# real_watch_1v1_displayboard.net
KiCad netlist of a schematic drawn in Altium Designer
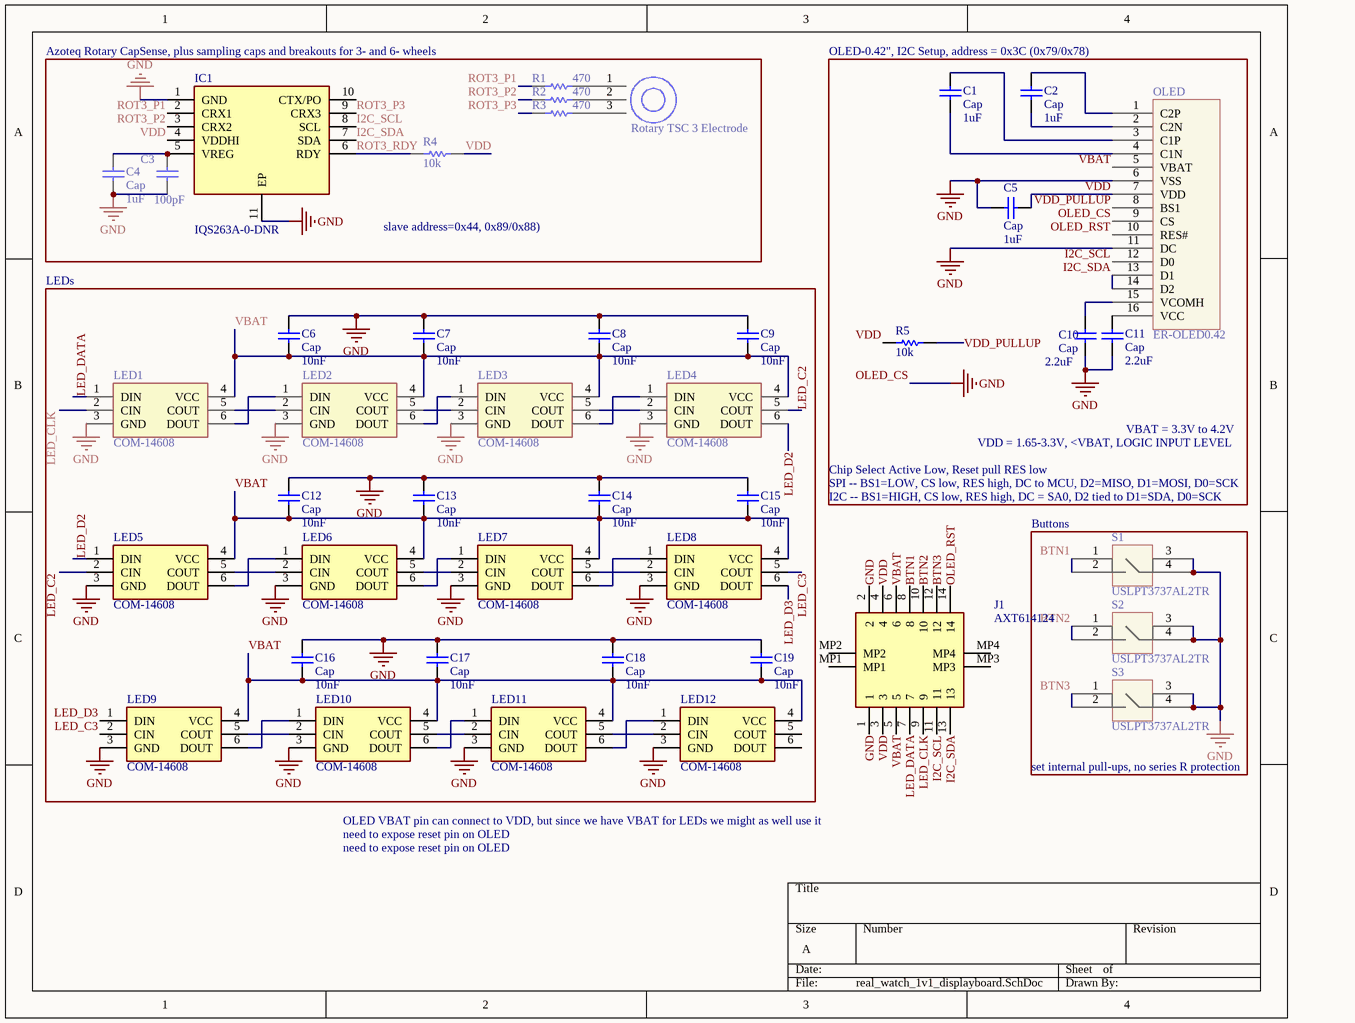
[diagram p0: real_watch_1v1_displayboard.SchDoc]

(export (version "E")
  (design (tool "Eeschema 10.0.6"))
  (components
    (comp (ref "C1")
      (value "Cap")
      (footprint "0402C")
      (description "Capacitor")
      (fields (field (name "ALTIUM_VALUE") "1uF") (field (name "PUBLISHER") "Altium Limited"))
      (libsource (lib "Miscellaneous Devices") (part "Cap"))
    )
    (comp (ref "C2")
      (value "Cap")
      (footprint "0402C")
      (description "Capacitor")
      (fields (field (name "ALTIUM_VALUE") "1uF") (field (name "PUBLISHER") "Altium Limited"))
      (libsource (lib "Miscellaneous Devices") (part "Cap"))
    )
    (comp (ref "C3")
      (value "100pF")
      (footprint "0402C")
      (description "Capacitor")
      (fields (field (name "Comment") "Cap") (field (name "PUBLISHER") "Altium Limited"))
      (libsource (lib "Miscellaneous Devices") (part "Cap"))
    )
    (comp (ref "C4")
      (value "Cap")
      (footprint "0402C")
      (description "Capacitor")
      (fields (field (name "ALTIUM_VALUE") "1uF") (field (name "PUBLISHER") "Altium Limited"))
      (libsource (lib "Miscellaneous Devices") (part "Cap"))
    )
    (comp (ref "C5")
      (value "Cap")
      (footprint "0402C")
      (description "Capacitor")
      (fields (field (name "ALTIUM_VALUE") "1uF") (field (name "PUBLISHER") "Altium Limited"))
      (libsource (lib "Miscellaneous Devices") (part "Cap"))
    )
    (comp (ref "C6")
      (value "Cap")
      (footprint "0402C")
      (description "Capacitor")
      (fields (field (name "ALTIUM_VALUE") "10nF") (field (name "PUBLISHER") "Altium Limited"))
      (libsource (lib "Miscellaneous Devices") (part "Cap"))
    )
    (comp (ref "C7")
      (value "Cap")
      (footprint "0402C")
      (description "Capacitor")
      (fields (field (name "ALTIUM_VALUE") "10nF") (field (name "PUBLISHER") "Altium Limited"))
      (libsource (lib "Miscellaneous Devices") (part "Cap"))
    )
    (comp (ref "C8")
      (value "Cap")
      (footprint "0402C")
      (description "Capacitor")
      (fields (field (name "ALTIUM_VALUE") "10nF") (field (name "PUBLISHER") "Altium Limited"))
      (libsource (lib "Miscellaneous Devices") (part "Cap"))
    )
    (comp (ref "C9")
      (value "Cap")
      (footprint "0402C")
      (description "Capacitor")
      (fields (field (name "ALTIUM_VALUE") "10nF") (field (name "PUBLISHER") "Altium Limited"))
      (libsource (lib "Miscellaneous Devices") (part "Cap"))
    )
    (comp (ref "C10")
      (value "Cap")
      (footprint "0402C")
      (description "Capacitor")
      (fields (field (name "ALTIUM_VALUE") "2.2uF") (field (name "PUBLISHER") "Altium Limited"))
      (libsource (lib "Miscellaneous Devices") (part "Cap"))
    )
    (comp (ref "C11")
      (value "Cap")
      (footprint "0402C")
      (description "Capacitor")
      (fields (field (name "ALTIUM_VALUE") "2.2uF") (field (name "PUBLISHER") "Altium Limited"))
      (libsource (lib "Miscellaneous Devices") (part "Cap"))
    )
    (comp (ref "C12")
      (value "Cap")
      (footprint "0402C")
      (description "Capacitor")
      (fields (field (name "ALTIUM_VALUE") "10nF") (field (name "PUBLISHER") "Altium Limited"))
      (libsource (lib "Miscellaneous Devices") (part "Cap"))
    )
    (comp (ref "C13")
      (value "Cap")
      (footprint "0402C")
      (description "Capacitor")
      (fields (field (name "ALTIUM_VALUE") "10nF") (field (name "PUBLISHER") "Altium Limited"))
      (libsource (lib "Miscellaneous Devices") (part "Cap"))
    )
    (comp (ref "C14")
      (value "Cap")
      (footprint "0402C")
      (description "Capacitor")
      (fields (field (name "ALTIUM_VALUE") "10nF") (field (name "PUBLISHER") "Altium Limited"))
      (libsource (lib "Miscellaneous Devices") (part "Cap"))
    )
    (comp (ref "C15")
      (value "Cap")
      (footprint "0402C")
      (description "Capacitor")
      (fields (field (name "ALTIUM_VALUE") "10nF") (field (name "PUBLISHER") "Altium Limited"))
      (libsource (lib "Miscellaneous Devices") (part "Cap"))
    )
    (comp (ref "C16")
      (value "Cap")
      (footprint "0402C")
      (description "Capacitor")
      (fields (field (name "ALTIUM_VALUE") "10nF") (field (name "PUBLISHER") "Altium Limited"))
      (libsource (lib "Miscellaneous Devices") (part "Cap"))
    )
    (comp (ref "C17")
      (value "Cap")
      (footprint "0402C")
      (description "Capacitor")
      (fields (field (name "ALTIUM_VALUE") "10nF") (field (name "PUBLISHER") "Altium Limited"))
      (libsource (lib "Miscellaneous Devices") (part "Cap"))
    )
    (comp (ref "C18")
      (value "Cap")
      (footprint "0402C")
      (description "Capacitor")
      (fields (field (name "ALTIUM_VALUE") "10nF") (field (name "PUBLISHER") "Altium Limited"))
      (libsource (lib "Miscellaneous Devices") (part "Cap"))
    )
    (comp (ref "C19")
      (value "Cap")
      (footprint "0402C")
      (description "Capacitor")
      (fields (field (name "ALTIUM_VALUE") "10nF") (field (name "PUBLISHER") "Altium Limited"))
      (libsource (lib "Miscellaneous Devices") (part "Cap"))
    )
    (comp (ref "IC1")
      (value "IQS263A-0-DNR")
      (footprint "SamacSys:SON50P300X300X80-11N-D")
      (description "Integrated Circuit")
      (libsource (lib "SamacSys") (part "IQS263A-0-DNR"))
    )
    (comp (ref "J1")
      (value "AXT614124")
      (footprint "SamacSys:AXT614124")
      (description "Connector")
      (fields (field (name "MOUSER PART NUMBER") "769-AXT614124"))
      (libsource (lib "*") (part "AXT614124"))
    )
    (comp (ref "LED1")
      (value "COM-14608")
      (footprint "SamacSys:SON75P200X200X100-6N")
      (description "LED")
      (fields (field (name "MOUSER PART NUMBER") "474-COM-14608"))
      (libsource (lib "*") (part "COM-14608"))
    )
    (comp (ref "LED2")
      (value "COM-14608")
      (footprint "SamacSys:SON75P200X200X100-6N")
      (description "LED")
      (fields (field (name "MOUSER PART NUMBER") "474-COM-14608"))
      (libsource (lib "*") (part "COM-14608"))
    )
    (comp (ref "LED3")
      (value "COM-14608")
      (footprint "SamacSys:SON75P200X200X100-6N")
      (description "LED")
      (fields (field (name "MOUSER PART NUMBER") "474-COM-14608"))
      (libsource (lib "*") (part "COM-14608"))
    )
    (comp (ref "LED4")
      (value "COM-14608")
      (footprint "SamacSys:SON75P200X200X100-6N")
      (description "LED")
      (fields (field (name "MOUSER PART NUMBER") "474-COM-14608"))
      (libsource (lib "*") (part "COM-14608"))
    )
    (comp (ref "LED5")
      (value "COM-14608")
      (footprint "SamacSys:SON75P200X200X100-6N")
      (description "LED")
      (fields (field (name "MOUSER PART NUMBER") "474-COM-14608"))
      (libsource (lib "*") (part "COM-14608"))
    )
    (comp (ref "LED6")
      (value "COM-14608")
      (footprint "SamacSys:SON75P200X200X100-6N")
      (description "LED")
      (fields (field (name "MOUSER PART NUMBER") "474-COM-14608"))
      (libsource (lib "*") (part "COM-14608"))
    )
    (comp (ref "LED7")
      (value "COM-14608")
      (footprint "SamacSys:SON75P200X200X100-6N")
      (description "LED")
      (fields (field (name "MOUSER PART NUMBER") "474-COM-14608"))
      (libsource (lib "*") (part "COM-14608"))
    )
    (comp (ref "LED8")
      (value "COM-14608")
      (footprint "SamacSys:SON75P200X200X100-6N")
      (description "LED")
      (fields (field (name "MOUSER PART NUMBER") "474-COM-14608"))
      (libsource (lib "*") (part "COM-14608"))
    )
    (comp (ref "LED9")
      (value "COM-14608")
      (footprint "SamacSys:SON75P200X200X100-6N")
      (description "LED")
      (fields (field (name "MOUSER PART NUMBER") "474-COM-14608"))
      (libsource (lib "*") (part "COM-14608"))
    )
    (comp (ref "LED10")
      (value "COM-14608")
      (footprint "SamacSys:SON75P200X200X100-6N")
      (description "LED")
      (fields (field (name "MOUSER PART NUMBER") "474-COM-14608"))
      (libsource (lib "*") (part "COM-14608"))
    )
    (comp (ref "LED11")
      (value "COM-14608")
      (footprint "SamacSys:SON75P200X200X100-6N")
      (description "LED")
      (fields (field (name "MOUSER PART NUMBER") "474-COM-14608"))
      (libsource (lib "*") (part "COM-14608"))
    )
    (comp (ref "LED12")
      (value "COM-14608")
      (footprint "SamacSys:SON75P200X200X100-6N")
      (description "LED")
      (fields (field (name "MOUSER PART NUMBER") "474-COM-14608"))
      (libsource (lib "*") (part "COM-14608"))
    )
    (comp (ref "OLED")
      (value "ER-OLED0.42")
      (footprint "ER-OLED-0.42")
      (description "BuyDisplay.com 0.42\" OLED Screen I2C/SPI")
      (libsource (lib "david_custom") (part "ER-OLED0.42"))
    )
    (comp (ref "R1")
      (value "470")
      (footprint "0402R")
      (libsource (lib "glasses_full_v1_small") (part "Resistor"))
    )
    (comp (ref "R2")
      (value "470")
      (footprint "0402R")
      (libsource (lib "glasses_full_v1_small") (part "Resistor"))
    )
    (comp (ref "R3")
      (value "470")
      (footprint "0402R")
      (libsource (lib "glasses_full_v1_small") (part "Resistor"))
    )
    (comp (ref "R4")
      (value "10k")
      (footprint "0402R")
      (libsource (lib "glasses_full_v1_small") (part "Resistor"))
    )
    (comp (ref "R5")
      (value "10k")
      (footprint "0402R")
      (libsource (lib "glasses_full_v1_small") (part "Resistor"))
    )
    (comp (ref "ROT1")
      (value "Rotary TSC 3 Electrode")
      (footprint "rotary_touch 3 electrode")
      (libsource (lib "david_custom") (part "Rotary TSC 3 Electrode"))
    )
    (comp (ref "S1")
      (value "USLPT3737AL2TR")
      (footprint "USLPT3737")
      (description "TE 0.35mm low profile switch")
      (libsource (lib "david_custom") (part "USLPT3737AL2TR"))
    )
    (comp (ref "S2")
      (value "USLPT3737AL2TR")
      (footprint "USLPT3737")
      (description "TE 0.35mm low profile switch")
      (libsource (lib "david_custom") (part "USLPT3737AL2TR"))
    )
    (comp (ref "S3")
      (value "USLPT3737AL2TR")
      (footprint "USLPT3737")
      (description "TE 0.35mm low profile switch")
      (libsource (lib "david_custom") (part "USLPT3737AL2TR"))
    )
  )
  (nets
    (net (code "1") (name "/BTN1") (class "Default")
      (node (ref "J1") (pin "8") (pinfunction "8_8") (pintype "passive"))
      (node (ref "S1") (pin "1") (pinfunction "L_1") (pintype "passive"))
      (node (ref "S1") (pin "2") (pinfunction "L_2") (pintype "passive"))
    )
    (net (code "2") (name "/BTN2") (class "Default")
      (node (ref "J1") (pin "10") (pinfunction "10_10") (pintype "passive"))
      (node (ref "S2") (pin "1") (pinfunction "L_1") (pintype "passive"))
      (node (ref "S2") (pin "2") (pinfunction "L_2") (pintype "passive"))
    )
    (net (code "3") (name "/BTN3") (class "Default")
      (node (ref "J1") (pin "12") (pinfunction "12_12") (pintype "passive"))
      (node (ref "S3") (pin "1") (pinfunction "L_1") (pintype "passive"))
      (node (ref "S3") (pin "2") (pinfunction "L_2") (pintype "passive"))
    )
    (net (code "4") (name "/I2C_SCL") (class "Default")
      (node (ref "IC1") (pin "8") (pinfunction "SCL_8") (pintype "passive"))
      (node (ref "J1") (pin "11") (pinfunction "11_11") (pintype "passive"))
      (node (ref "OLED") (pin "12") (pinfunction "D0_12") (pintype "passive"))
    )
    (net (code "5") (name "/I2C_SDA") (class "Default")
      (node (ref "IC1") (pin "7") (pinfunction "SDA_7") (pintype "passive"))
      (node (ref "J1") (pin "13") (pinfunction "13_13") (pintype "passive"))
      (node (ref "OLED") (pin "13") (pinfunction "D1_13") (pintype "passive"))
      (node (ref "OLED") (pin "14") (pinfunction "D2_14") (pintype "passive"))
    )
    (net (code "6") (name "/LED_C2") (class "Default")
      (node (ref "LED4") (pin "5") (pinfunction "COUT_5") (pintype "passive"))
      (node (ref "LED5") (pin "2") (pinfunction "CIN_2") (pintype "passive"))
    )
    (net (code "7") (name "/LED_C3") (class "Default")
      (node (ref "LED8") (pin "5") (pinfunction "COUT_5") (pintype "passive"))
      (node (ref "LED9") (pin "2") (pinfunction "CIN_2") (pintype "passive"))
    )
    (net (code "8") (name "/LED_CLK") (class "Default")
      (node (ref "J1") (pin "9") (pinfunction "9_9") (pintype "passive"))
      (node (ref "LED1") (pin "2") (pinfunction "CIN_2") (pintype "passive"))
    )
    (net (code "9") (name "/LED_D2") (class "Default")
      (node (ref "LED4") (pin "6") (pinfunction "DOUT_6") (pintype "passive"))
      (node (ref "LED5") (pin "1") (pinfunction "DIN_1") (pintype "passive"))
    )
    (net (code "10") (name "/LED_D3") (class "Default")
      (node (ref "LED8") (pin "6") (pinfunction "DOUT_6") (pintype "passive"))
      (node (ref "LED9") (pin "1") (pinfunction "DIN_1") (pintype "passive"))
    )
    (net (code "11") (name "/LED_DATA") (class "Default")
      (node (ref "J1") (pin "7") (pinfunction "7_7") (pintype "passive"))
      (node (ref "LED1") (pin "1") (pinfunction "DIN_1") (pintype "passive"))
    )
    (net (code "12") (name "/OLED_RST") (class "Default")
      (node (ref "J1") (pin "14") (pinfunction "14_14") (pintype "passive"))
      (node (ref "OLED") (pin "10") (pinfunction "RES#_10") (pintype "passive"))
    )
    (net (code "13") (name "/ROT3_P1") (class "Default")
      (node (ref "IC1") (pin "2") (pinfunction "CRX1_2") (pintype "passive"))
      (node (ref "R1") (pin "2") (pinfunction "2_2") (pintype "passive"))
    )
    (net (code "14") (name "/ROT3_P2") (class "Default")
      (node (ref "IC1") (pin "3") (pinfunction "CRX2_3") (pintype "passive"))
      (node (ref "R2") (pin "2") (pinfunction "2_2") (pintype "passive"))
    )
    (net (code "15") (name "/ROT3_P3") (class "Default")
      (node (ref "IC1") (pin "9") (pinfunction "CRX3_9") (pintype "passive"))
      (node (ref "R3") (pin "2") (pinfunction "2_2") (pintype "passive"))
    )
    (net (code "16") (name "/ROT3_RDY") (class "Default")
      (node (ref "IC1") (pin "6") (pinfunction "RDY_6") (pintype "passive"))
      (node (ref "R4") (pin "1") (pinfunction "1_1") (pintype "passive"))
    )
    (net (code "17") (name "/VBAT") (class "Default")
      (node (ref "C12") (pin "1") (pinfunction "1_1") (pintype "passive"))
      (node (ref "C13") (pin "1") (pinfunction "1_1") (pintype "passive"))
      (node (ref "C14") (pin "1") (pinfunction "1_1") (pintype "passive"))
      (node (ref "C15") (pin "1") (pinfunction "1_1") (pintype "passive"))
      (node (ref "C16") (pin "1") (pinfunction "1_1") (pintype "passive"))
      (node (ref "C17") (pin "1") (pinfunction "1_1") (pintype "passive"))
      (node (ref "C18") (pin "1") (pinfunction "1_1") (pintype "passive"))
      (node (ref "C19") (pin "1") (pinfunction "1_1") (pintype "passive"))
      (node (ref "C6") (pin "1") (pinfunction "1_1") (pintype "passive"))
      (node (ref "C7") (pin "1") (pinfunction "1_1") (pintype "passive"))
      (node (ref "C8") (pin "1") (pinfunction "1_1") (pintype "passive"))
      (node (ref "C9") (pin "1") (pinfunction "1_1") (pintype "passive"))
      (node (ref "J1") (pin "5") (pinfunction "5_5") (pintype "passive"))
      (node (ref "J1") (pin "6") (pinfunction "6_6") (pintype "passive"))
      (node (ref "LED1") (pin "4") (pinfunction "VCC_4") (pintype "passive"))
      (node (ref "LED10") (pin "4") (pinfunction "VCC_4") (pintype "passive"))
      (node (ref "LED11") (pin "4") (pinfunction "VCC_4") (pintype "passive"))
      (node (ref "LED12") (pin "4") (pinfunction "VCC_4") (pintype "passive"))
      (node (ref "LED2") (pin "4") (pinfunction "VCC_4") (pintype "passive"))
      (node (ref "LED3") (pin "4") (pinfunction "VCC_4") (pintype "passive"))
      (node (ref "LED4") (pin "4") (pinfunction "VCC_4") (pintype "passive"))
      (node (ref "LED5") (pin "4") (pinfunction "VCC_4") (pintype "passive"))
      (node (ref "LED6") (pin "4") (pinfunction "VCC_4") (pintype "passive"))
      (node (ref "LED7") (pin "4") (pinfunction "VCC_4") (pintype "passive"))
      (node (ref "LED8") (pin "4") (pinfunction "VCC_4") (pintype "passive"))
      (node (ref "LED9") (pin "4") (pinfunction "VCC_4") (pintype "passive"))
      (node (ref "OLED") (pin "5") (pinfunction "VBAT_5") (pintype "power_in"))
    )
    (net (code "18") (name "/VDD") (class "Default")
      (node (ref "C5") (pin "2") (pinfunction "2_2") (pintype "passive"))
      (node (ref "IC1") (pin "4") (pinfunction "VDDHI_4") (pintype "passive"))
      (node (ref "J1") (pin "3") (pinfunction "3_3") (pintype "passive"))
      (node (ref "J1") (pin "4") (pinfunction "4_4") (pintype "passive"))
      (node (ref "OLED") (pin "7") (pinfunction "VDD_7") (pintype "passive"))
      (node (ref "R4") (pin "2") (pinfunction "2_2") (pintype "passive"))
      (node (ref "R5") (pin "1") (pinfunction "1_1") (pintype "passive"))
    )
    (net (code "19") (name "/VDD_PULLUP") (class "Default")
      (node (ref "OLED") (pin "8") (pinfunction "BS1_8") (pintype "passive"))
      (node (ref "R5") (pin "2") (pinfunction "2_2") (pintype "passive"))
    )
    (net (code "20") (name "GND") (class "Default")
      (node (ref "C10") (pin "1") (pinfunction "1_1") (pintype "passive"))
      (node (ref "C11") (pin "1") (pinfunction "1_1") (pintype "passive"))
      (node (ref "C12") (pin "2") (pinfunction "2_2") (pintype "passive"))
      (node (ref "C13") (pin "2") (pinfunction "2_2") (pintype "passive"))
      (node (ref "C14") (pin "2") (pinfunction "2_2") (pintype "passive"))
      (node (ref "C15") (pin "2") (pinfunction "2_2") (pintype "passive"))
      (node (ref "C16") (pin "2") (pinfunction "2_2") (pintype "passive"))
      (node (ref "C17") (pin "2") (pinfunction "2_2") (pintype "passive"))
      (node (ref "C18") (pin "2") (pinfunction "2_2") (pintype "passive"))
      (node (ref "C19") (pin "2") (pinfunction "2_2") (pintype "passive"))
      (node (ref "C3") (pin "1") (pinfunction "1_1") (pintype "passive"))
      (node (ref "C4") (pin "1") (pinfunction "1_1") (pintype "passive"))
      (node (ref "C5") (pin "1") (pinfunction "1_1") (pintype "passive"))
      (node (ref "C6") (pin "2") (pinfunction "2_2") (pintype "passive"))
      (node (ref "C7") (pin "2") (pinfunction "2_2") (pintype "passive"))
      (node (ref "C8") (pin "2") (pinfunction "2_2") (pintype "passive"))
      (node (ref "C9") (pin "2") (pinfunction "2_2") (pintype "passive"))
      (node (ref "IC1") (pin "1") (pinfunction "GND_1") (pintype "passive"))
      (node (ref "IC1") (pin "11") (pinfunction "EP_11") (pintype "passive"))
      (node (ref "J1") (pin "1") (pinfunction "1_1") (pintype "passive"))
      (node (ref "J1") (pin "2") (pinfunction "2_2") (pintype "passive"))
      (node (ref "LED1") (pin "3") (pinfunction "GND_3") (pintype "passive"))
      (node (ref "LED10") (pin "3") (pinfunction "GND_3") (pintype "passive"))
      (node (ref "LED11") (pin "3") (pinfunction "GND_3") (pintype "passive"))
      (node (ref "LED12") (pin "3") (pinfunction "GND_3") (pintype "passive"))
      (node (ref "LED2") (pin "3") (pinfunction "GND_3") (pintype "passive"))
      (node (ref "LED3") (pin "3") (pinfunction "GND_3") (pintype "passive"))
      (node (ref "LED4") (pin "3") (pinfunction "GND_3") (pintype "passive"))
      (node (ref "LED5") (pin "3") (pinfunction "GND_3") (pintype "passive"))
      (node (ref "LED6") (pin "3") (pinfunction "GND_3") (pintype "passive"))
      (node (ref "LED7") (pin "3") (pinfunction "GND_3") (pintype "passive"))
      (node (ref "LED8") (pin "3") (pinfunction "GND_3") (pintype "passive"))
      (node (ref "LED9") (pin "3") (pinfunction "GND_3") (pintype "passive"))
      (node (ref "OLED") (pin "11") (pinfunction "DC_11") (pintype "passive"))
      (node (ref "OLED") (pin "6") (pinfunction "VSS_6") (pintype "passive"))
      (node (ref "OLED") (pin "9") (pinfunction "CS_9") (pintype "passive"))
      (node (ref "S1") (pin "3") (pinfunction "R_3") (pintype "passive"))
      (node (ref "S1") (pin "4") (pinfunction "R_4") (pintype "passive"))
      (node (ref "S2") (pin "3") (pinfunction "R_3") (pintype "passive"))
      (node (ref "S2") (pin "4") (pinfunction "R_4") (pintype "passive"))
      (node (ref "S3") (pin "3") (pinfunction "R_3") (pintype "passive"))
      (node (ref "S3") (pin "4") (pinfunction "R_4") (pintype "passive"))
    )
    (net (code "21") (name "Net-(IC1-VREG)") (class "Default")
      (node (ref "C3") (pin "2") (pinfunction "2_2") (pintype "passive"))
      (node (ref "C4") (pin "2") (pinfunction "2_2") (pintype "passive"))
      (node (ref "IC1") (pin "5") (pinfunction "VREG_5") (pintype "passive"))
    )
    (net (code "22") (name "Net-(LED1-COUT)") (class "Default")
      (node (ref "LED1") (pin "5") (pinfunction "COUT_5") (pintype "passive"))
      (node (ref "LED2") (pin "2") (pinfunction "CIN_2") (pintype "passive"))
    )
    (net (code "23") (name "Net-(LED1-DOUT)") (class "Default")
      (node (ref "LED1") (pin "6") (pinfunction "DOUT_6") (pintype "passive"))
      (node (ref "LED2") (pin "1") (pinfunction "DIN_1") (pintype "passive"))
    )
    (net (code "24") (name "Net-(LED2-COUT)") (class "Default")
      (node (ref "LED2") (pin "5") (pinfunction "COUT_5") (pintype "passive"))
      (node (ref "LED3") (pin "2") (pinfunction "CIN_2") (pintype "passive"))
    )
    (net (code "25") (name "Net-(LED2-DOUT)") (class "Default")
      (node (ref "LED2") (pin "6") (pinfunction "DOUT_6") (pintype "passive"))
      (node (ref "LED3") (pin "1") (pinfunction "DIN_1") (pintype "passive"))
    )
    (net (code "26") (name "Net-(LED3-COUT)") (class "Default")
      (node (ref "LED3") (pin "5") (pinfunction "COUT_5") (pintype "passive"))
      (node (ref "LED4") (pin "2") (pinfunction "CIN_2") (pintype "passive"))
    )
    (net (code "27") (name "Net-(LED3-DOUT)") (class "Default")
      (node (ref "LED3") (pin "6") (pinfunction "DOUT_6") (pintype "passive"))
      (node (ref "LED4") (pin "1") (pinfunction "DIN_1") (pintype "passive"))
    )
    (net (code "28") (name "Net-(LED5-COUT)") (class "Default")
      (node (ref "LED5") (pin "5") (pinfunction "COUT_5") (pintype "passive"))
      (node (ref "LED6") (pin "2") (pinfunction "CIN_2") (pintype "passive"))
    )
    (net (code "29") (name "Net-(LED5-DOUT)") (class "Default")
      (node (ref "LED5") (pin "6") (pinfunction "DOUT_6") (pintype "passive"))
      (node (ref "LED6") (pin "1") (pinfunction "DIN_1") (pintype "passive"))
    )
    (net (code "30") (name "Net-(LED6-COUT)") (class "Default")
      (node (ref "LED6") (pin "5") (pinfunction "COUT_5") (pintype "passive"))
      (node (ref "LED7") (pin "2") (pinfunction "CIN_2") (pintype "passive"))
    )
    (net (code "31") (name "Net-(LED6-DOUT)") (class "Default")
      (node (ref "LED6") (pin "6") (pinfunction "DOUT_6") (pintype "passive"))
      (node (ref "LED7") (pin "1") (pinfunction "DIN_1") (pintype "passive"))
    )
    (net (code "32") (name "Net-(LED7-COUT)") (class "Default")
      (node (ref "LED7") (pin "5") (pinfunction "COUT_5") (pintype "passive"))
      (node (ref "LED8") (pin "2") (pinfunction "CIN_2") (pintype "passive"))
    )
    (net (code "33") (name "Net-(LED7-DOUT)") (class "Default")
      (node (ref "LED7") (pin "6") (pinfunction "DOUT_6") (pintype "passive"))
      (node (ref "LED8") (pin "1") (pinfunction "DIN_1") (pintype "passive"))
    )
    (net (code "34") (name "Net-(LED10-CIN)") (class "Default")
      (node (ref "LED10") (pin "2") (pinfunction "CIN_2") (pintype "passive"))
      (node (ref "LED9") (pin "5") (pinfunction "COUT_5") (pintype "passive"))
    )
    (net (code "35") (name "Net-(LED10-COUT)") (class "Default")
      (node (ref "LED10") (pin "5") (pinfunction "COUT_5") (pintype "passive"))
      (node (ref "LED11") (pin "2") (pinfunction "CIN_2") (pintype "passive"))
    )
    (net (code "36") (name "Net-(LED10-DIN)") (class "Default")
      (node (ref "LED10") (pin "1") (pinfunction "DIN_1") (pintype "passive"))
      (node (ref "LED9") (pin "6") (pinfunction "DOUT_6") (pintype "passive"))
    )
    (net (code "37") (name "Net-(LED10-DOUT)") (class "Default")
      (node (ref "LED10") (pin "6") (pinfunction "DOUT_6") (pintype "passive"))
      (node (ref "LED11") (pin "1") (pinfunction "DIN_1") (pintype "passive"))
    )
    (net (code "38") (name "Net-(LED11-COUT)") (class "Default")
      (node (ref "LED11") (pin "5") (pinfunction "COUT_5") (pintype "passive"))
      (node (ref "LED12") (pin "2") (pinfunction "CIN_2") (pintype "passive"))
    )
    (net (code "39") (name "Net-(LED11-DOUT)") (class "Default")
      (node (ref "LED11") (pin "6") (pinfunction "DOUT_6") (pintype "passive"))
      (node (ref "LED12") (pin "1") (pinfunction "DIN_1") (pintype "passive"))
    )
    (net (code "40") (name "Net-(OLED-C1N)") (class "Default")
      (node (ref "C1") (pin "1") (pinfunction "1_1") (pintype "passive"))
      (node (ref "OLED") (pin "4") (pinfunction "C1N_4") (pintype "passive"))
    )
    (net (code "41") (name "Net-(OLED-C1P)") (class "Default")
      (node (ref "C1") (pin "2") (pinfunction "2_2") (pintype "passive"))
      (node (ref "OLED") (pin "3") (pinfunction "C1P_3") (pintype "passive"))
    )
    (net (code "42") (name "Net-(OLED-C2N)") (class "Default")
      (node (ref "C2") (pin "1") (pinfunction "1_1") (pintype "passive"))
      (node (ref "OLED") (pin "2") (pinfunction "C2N_2") (pintype "passive"))
    )
    (net (code "43") (name "Net-(OLED-C2P)") (class "Default")
      (node (ref "C2") (pin "2") (pinfunction "2_2") (pintype "passive"))
      (node (ref "OLED") (pin "1") (pinfunction "C2P_1") (pintype "passive"))
    )
    (net (code "44") (name "Net-(OLED-VCC)") (class "Default")
      (node (ref "C11") (pin "2") (pinfunction "2_2") (pintype "passive"))
      (node (ref "OLED") (pin "16") (pinfunction "VCC_16") (pintype "power_in"))
    )
    (net (code "45") (name "Net-(OLED-VCOMH)") (class "Default")
      (node (ref "C10") (pin "2") (pinfunction "2_2") (pintype "passive"))
      (node (ref "OLED") (pin "15") (pinfunction "VCOMH_15") (pintype "passive"))
    )
    (net (code "46") (name "Net-(ROT1-e1)") (class "Default")
      (node (ref "R1") (pin "1") (pinfunction "1_1") (pintype "passive"))
      (node (ref "ROT1") (pin "1") (pinfunction "e1_1") (pintype "passive"))
    )
    (net (code "47") (name "Net-(ROT1-e2)") (class "Default")
      (node (ref "R2") (pin "1") (pinfunction "1_1") (pintype "passive"))
      (node (ref "ROT1") (pin "2") (pinfunction "e2_2") (pintype "passive"))
    )
    (net (code "48") (name "Net-(ROT1-e3)") (class "Default")
      (node (ref "R3") (pin "1") (pinfunction "1_1") (pintype "passive"))
      (node (ref "ROT1") (pin "3") (pinfunction "e3_3") (pintype "passive"))
    )
    (net (code "49") (name "unconnected-(IC1-CTX{slash}PO-Pad10)") (class "Default")
      (node (ref "IC1") (pin "10") (pinfunction "CTX/PO_10") (pintype "passive"))
    )
    (net (code "50") (name "unconnected-(J1-PadMP1)") (class "Default")
      (node (ref "J1") (pin "MP1") (pinfunction "MP1_MP1") (pintype "passive"))
    )
    (net (code "51") (name "unconnected-(J1-PadMP2)") (class "Default")
      (node (ref "J1") (pin "MP2") (pinfunction "MP2_MP2") (pintype "passive"))
    )
    (net (code "52") (name "unconnected-(J1-PadMP3)") (class "Default")
      (node (ref "J1") (pin "MP3") (pinfunction "MP3_MP3") (pintype "passive"))
    )
    (net (code "53") (name "unconnected-(J1-PadMP4)") (class "Default")
      (node (ref "J1") (pin "MP4") (pinfunction "MP4_MP4") (pintype "passive"))
    )
    (net (code "54") (name "unconnected-(LED12-COUT-Pad5)") (class "Default")
      (node (ref "LED12") (pin "5") (pinfunction "COUT_5") (pintype "passive"))
    )
    (net (code "55") (name "unconnected-(LED12-DOUT-Pad6)") (class "Default")
      (node (ref "LED12") (pin "6") (pinfunction "DOUT_6") (pintype "passive"))
    )
  )
)
